# 03_DCDC_BOOST.net
KiCad netlist of a schematic drawn in Altium Designer
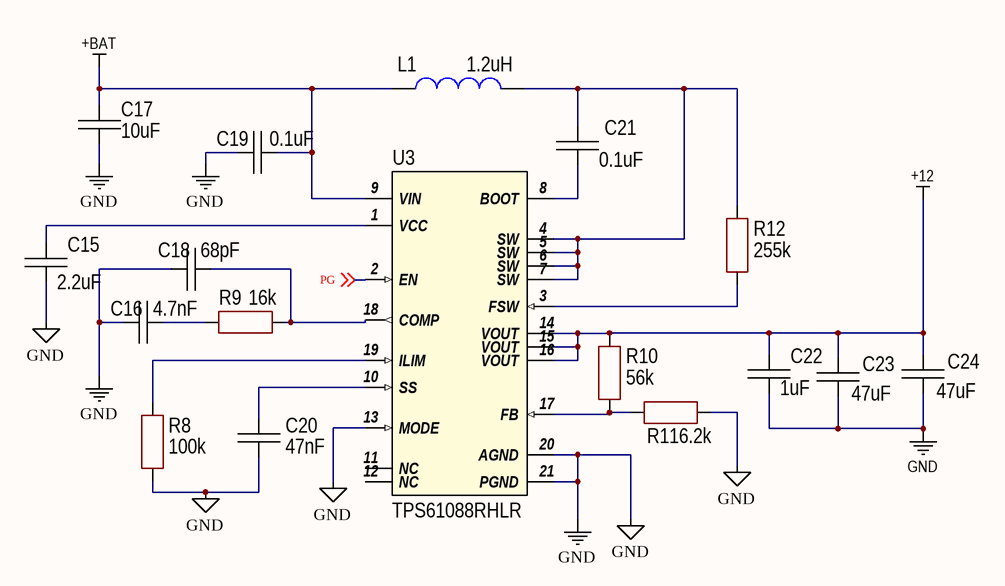
[diagram p0: 03_DCDC_BOOST.SchDoc]

(export (version "E")
  (design (tool "Eeschema 10.0.6"))
  (components
    (comp (ref "C15")
      (value "2.2uF")
      (footprint "CAP: 0805")
      (fields
        (field (name "MANUFACTURER") "Yageo")
        (field (name "PARTNUMBER") "CC0805KRX7R7BB104")
        (field (name "VALUEMANUFACTURERPARTNUMBER") "Ceramic capacitor, 2.2uF, X7R, ±10%, 16V, 0805, -55...+125°C")
      )
      (libsource (lib "capacitor") (part "Ceramic_0805"))
    )
    (comp (ref "C16")
      (value "4.7nF")
      (footprint "CAP: 0805")
      (fields
        (field (name "MANUFACTURER") "Yageo")
        (field (name "PARTNUMBER") "CC0805KRX7R7BB104")
        (field (name "VALUEMANUFACTURERPARTNUMBER") "Ceramic capacitor, 4.7nF, X7R, ±10%, 16V, 0805, -55...+125°C")
      )
      (libsource (lib "capacitor") (part "Ceramic_0805"))
    )
    (comp (ref "C17")
      (value "10uF")
      (footprint "CAP: 1206")
      (fields
        (field (name "MANUFACTURER") "Yageo")
        (field (name "PARTNUMBER") "CC1206KRX7R9BB104")
        (field (name "VALUEMANUFACTURERPARTNUMBER") "Ceramic capacitor, 10uF, X7R, ±10%, 50V, 1206, -55...+125°C")
      )
      (libsource (lib "capacitor") (part "Ceramic_1206"))
    )
    (comp (ref "C18")
      (value "68pF")
      (footprint "CAP: 0805")
      (fields
        (field (name "MANUFACTURER") "Yageo")
        (field (name "PARTNUMBER") "CC0805KRX7R7BB104")
        (field (name "VALUEMANUFACTURERPARTNUMBER") "Ceramic capacitor, 68pF, X7R, ±10%, 16V, 0805, -55...+125°C")
      )
      (libsource (lib "capacitor") (part "Ceramic_0805"))
    )
    (comp (ref "C19")
      (value "0.1uF")
      (footprint "CAP: 0603")
      (fields
        (field (name "MANUFACTURER") "Yageo")
        (field (name "PARTNUMBER") "CC0603KRX7R7BB104")
        (field (name "VALUEMANUFACTURERPARTNUMBER") "Ceramic capacitor, 0.1uF, X7R, ±10%, 16V, 0603, -55...+125°C")
      )
      (libsource (lib "capacitor") (part "Ceramic_0603"))
    )
    (comp (ref "C20")
      (value "47nF")
      (footprint "CAP: 0603")
      (fields
        (field (name "MANUFACTURER") "Yageo")
        (field (name "PARTNUMBER") "CC0603KRX7R7BB104")
        (field (name "VALUEMANUFACTURERPARTNUMBER") "Ceramic capacitor, 47nF, X7R, ±10%, 16V, 0603, -55...+125°C")
      )
      (libsource (lib "capacitor") (part "Ceramic_0603"))
    )
    (comp (ref "C21")
      (value "0.1uF")
      (footprint "CAP: 1210")
      (fields
        (field (name "MANUFACTURER") "Yageo")
        (field (name "PARTNUMBER") "CC1210KKX7R9BB104")
        (field (name "VALUEMANUFACTURERPARTNUMBER") "Ceramic capacitor, 0.1uF, X7R, ±10%, 50V, 1210, -55...+125°C")
      )
      (libsource (lib "capacitor") (part "Ceramic_1210"))
    )
    (comp (ref "C22")
      (value "1uF")
      (footprint "CAP: 0805")
      (fields
        (field (name "MANUFACTURER") "Yageo")
        (field (name "PARTNUMBER") "CC0805KRX7R7BB104")
        (field (name "VALUEMANUFACTURERPARTNUMBER") "Ceramic capacitor, 1uF, X7R, ±10%, 16V, 0805, -55...+125°C")
      )
      (libsource (lib "capacitor") (part "Ceramic_0805"))
    )
    (comp (ref "C23")
      (value "47uF")
      (footprint "CAP: 1206")
      (fields
        (field (name "MANUFACTURER") "Yageo")
        (field (name "PARTNUMBER") "CC1206KRX7R9BB104")
        (field (name "VALUEMANUFACTURERPARTNUMBER") "Ceramic capacitor, 47uF, X7R, ±10%, 50V, 1206, -55...+125°C")
      )
      (libsource (lib "capacitor") (part "Ceramic_1206"))
    )
    (comp (ref "C24")
      (value "47uF")
      (footprint "CAP: 1206")
      (fields
        (field (name "MANUFACTURER") "Yageo")
        (field (name "PARTNUMBER") "CC1206KRX7R9BB104")
        (field (name "VALUEMANUFACTURERPARTNUMBER") "Ceramic capacitor, 47uF, X7R, ±10%, 50V, 1206, -55...+125°C")
      )
      (libsource (lib "capacitor") (part "Ceramic_1206"))
    )
    (comp (ref "L1")
      (value "1.2uH")
      (footprint "IND: SRP1265A")
      (fields
        (field (name "MANUFACTURER") "Bourns")
        (field (name "PARTNUMBER") "SRP1265A-4R7M")
        (field (name "VALUEMANUFACTURERPARTNUMBER") "Fixed inductor, 1.2uH, ±20%, SRP1265A, 13.5A, -40...+150°C")
      )
      (libsource (lib "inductor") (part "Inductor_SRP1265A"))
    )
    (comp (ref "R8")
      (value "100k")
      (footprint "RES: 0603")
      (fields
        (field (name "MANUFACTURER") "Yageo")
        (field (name "PARTNUMBER") "RC0603JR-07100RL")
        (field (name "VALUEMANUFACTURERPARTNUMBER") "Resistor film, 100k, ±5%, 0603, 0.1W, -55...+125°C")
      )
      (libsource (lib "resistor") (part "Resistor_0603"))
    )
    (comp (ref "R9")
      (value "16k")
      (footprint "RES: 0603")
      (fields
        (field (name "MANUFACTURER") "Yageo")
        (field (name "PARTNUMBER") "RC0603JR-07100RL")
        (field (name "VALUEMANUFACTURERPARTNUMBER") "Resistor film, 16k, ±5%, 0603, 0.1W, -55...+125°C")
      )
      (libsource (lib "") (part "Resistor_0603_1"))
    )
    (comp (ref "R10")
      (value "56k")
      (footprint "RES: 0603")
      (fields
        (field (name "MANUFACTURER") "Yageo")
        (field (name "PARTNUMBER") "RC0603JR-07100RL")
        (field (name "VALUEMANUFACTURERPARTNUMBER") "Resistor film, 56k, ±5%, 0603, 0.1W, -55...+125°C")
      )
      (libsource (lib "resistor") (part "Resistor_0603"))
    )
    (comp (ref "R11")
      (value "6.2k")
      (footprint "RES: 0603")
      (fields
        (field (name "MANUFACTURER") "Yageo")
        (field (name "PARTNUMBER") "RC0603JR-07100RL")
        (field (name "VALUEMANUFACTURERPARTNUMBER") "Resistor film, 6.2k, ±5%, 0603, 0.1W, -55...+125°C")
      )
      (libsource (lib "") (part "Resistor_0603_1"))
    )
    (comp (ref "R12")
      (value "255k")
      (footprint "RES: 0603")
      (fields
        (field (name "MANUFACTURER") "Yageo")
        (field (name "PARTNUMBER") "RC0603JR-07100RL")
        (field (name "VALUEMANUFACTURERPARTNUMBER") "Resistor film, 255k, ±5%, 0603, 0.1W, -55...+125°C")
      )
      (libsource (lib "resistor") (part "Resistor_0603"))
    )
    (comp (ref "U3")
      (value "TPS61088RHLR")
      (footprint "RHL0020A")
      (description "10-A Fully-Integrated Synchronous Boost Converter 20-VQFN -40 to 125")
      (fields
        (field (name "ALTERNATE_PARTNUMBER") "TPS61088RHLT")
        (field (name "MANUFACTURER") "Texas Instruments")
        (field (name "COPYRIGHT") "Copyright (C) 2026 Ultra Librarian. All rights reserved.")
      )
      (libsource (lib "TPS61088RHLR") (part "TPS61088RHLR"))
    )
  )
  (nets
    (net (code "1") (name "+12") (class "Default")
      (node (ref "C22") (pin "2") (pinfunction "2_2") (pintype "passive"))
      (node (ref "C23") (pin "2") (pinfunction "2_2") (pintype "passive"))
      (node (ref "C24") (pin "2") (pinfunction "2_2") (pintype "passive"))
      (node (ref "R10") (pin "2") (pinfunction "2_2") (pintype "passive"))
      (node (ref "U3") (pin "14") (pinfunction "VOUT_14") (pintype "power_in"))
      (node (ref "U3") (pin "15") (pinfunction "VOUT_15") (pintype "power_in"))
      (node (ref "U3") (pin "16") (pinfunction "VOUT_16") (pintype "power_in"))
    )
    (net (code "2") (name "+BAT") (class "Default")
      (node (ref "C17") (pin "1") (pinfunction "1_1") (pintype "passive"))
      (node (ref "C19") (pin "1") (pinfunction "1_1") (pintype "passive"))
      (node (ref "L1") (pin "2") (pinfunction "2_2") (pintype "passive"))
      (node (ref "U3") (pin "9") (pinfunction "VIN_9") (pintype "power_in"))
    )
    (net (code "3") (name "GND") (class "Default")
      (node (ref "C15") (pin "1") (pinfunction "1_1") (pintype "passive"))
      (node (ref "C16") (pin "2") (pinfunction "2_2") (pintype "passive"))
      (node (ref "C17") (pin "2") (pinfunction "2_2") (pintype "passive"))
      (node (ref "C18") (pin "2") (pinfunction "2_2") (pintype "passive"))
      (node (ref "C19") (pin "2") (pinfunction "2_2") (pintype "passive"))
      (node (ref "C20") (pin "1") (pinfunction "1_1") (pintype "passive"))
      (node (ref "C22") (pin "1") (pinfunction "1_1") (pintype "passive"))
      (node (ref "C23") (pin "1") (pinfunction "1_1") (pintype "passive"))
      (node (ref "C24") (pin "1") (pinfunction "1_1") (pintype "passive"))
      (node (ref "R11") (pin "2") (pinfunction "2_2") (pintype "passive"))
      (node (ref "R8") (pin "1") (pinfunction "1_1") (pintype "passive"))
      (node (ref "U3") (pin "13") (pinfunction "MODE_13") (pintype "input"))
      (node (ref "U3") (pin "20") (pinfunction "AGND_20") (pintype "power_in"))
      (node (ref "U3") (pin "21") (pinfunction "PGND_21") (pintype "power_in"))
    )
    (net (code "4") (name "Net-(C16-Pad1)") (class "Default")
      (node (ref "C16") (pin "1") (pinfunction "1_1") (pintype "passive"))
      (node (ref "R9") (pin "1") (pinfunction "1_1") (pintype "passive"))
    )
    (net (code "5") (name "Net-(C21-Pad2)") (class "Default")
      (node (ref "C21") (pin "2") (pinfunction "2_2") (pintype "passive"))
      (node (ref "L1") (pin "1") (pinfunction "1_1") (pintype "passive"))
      (node (ref "R12") (pin "2") (pinfunction "2_2") (pintype "passive"))
      (node (ref "U3") (pin "4") (pinfunction "SW_4") (pintype "power_in"))
      (node (ref "U3") (pin "5") (pinfunction "SW_5") (pintype "power_in"))
      (node (ref "U3") (pin "6") (pinfunction "SW_6") (pintype "power_in"))
      (node (ref "U3") (pin "7") (pinfunction "SW_7") (pintype "power_in"))
    )
    (net (code "6") (name "Net-(U3-BOOT)") (class "Default")
      (node (ref "C21") (pin "1") (pinfunction "1_1") (pintype "passive"))
      (node (ref "U3") (pin "8") (pinfunction "BOOT_8") (pintype "power_in"))
    )
    (net (code "7") (name "Net-(U3-COMP)") (class "Default")
      (node (ref "C18") (pin "1") (pinfunction "1_1") (pintype "passive"))
      (node (ref "R9") (pin "2") (pinfunction "2_2") (pintype "passive"))
      (node (ref "U3") (pin "18") (pinfunction "COMP_18") (pintype "output"))
    )
    (net (code "8") (name "Net-(U3-FB)") (class "Default")
      (node (ref "R10") (pin "1") (pinfunction "1_1") (pintype "passive"))
      (node (ref "R11") (pin "1") (pinfunction "1_1") (pintype "passive"))
      (node (ref "U3") (pin "17") (pinfunction "FB_17") (pintype "input"))
    )
    (net (code "9") (name "Net-(U3-FSW)") (class "Default")
      (node (ref "R12") (pin "1") (pinfunction "1_1") (pintype "passive"))
      (node (ref "U3") (pin "3") (pinfunction "FSW_3") (pintype "input"))
    )
    (net (code "10") (name "Net-(U3-ILIM)") (class "Default")
      (node (ref "R8") (pin "2") (pinfunction "2_2") (pintype "passive"))
      (node (ref "U3") (pin "19") (pinfunction "ILIM_19") (pintype "input"))
    )
    (net (code "11") (name "Net-(U3-SS)") (class "Default")
      (node (ref "C20") (pin "2") (pinfunction "2_2") (pintype "passive"))
      (node (ref "U3") (pin "10") (pinfunction "SS_10") (pintype "input"))
    )
    (net (code "12") (name "Net-(U3-VCC)") (class "Default")
      (node (ref "C15") (pin "2") (pinfunction "2_2") (pintype "passive"))
      (node (ref "U3") (pin "1") (pinfunction "VCC_1") (pintype "power_in"))
    )
    (net (code "13") (name "PG") (class "Default")
      (node (ref "U3") (pin "2") (pinfunction "EN_2") (pintype "input"))
    )
    (net (code "14") (name "unconnected-(U3-NC-Pad11)") (class "Default")
      (node (ref "U3") (pin "11") (pinfunction "NC_11") (pintype "passive"))
    )
    (net (code "15") (name "unconnected-(U3-NC-Pad12)") (class "Default")
      (node (ref "U3") (pin "12") (pinfunction "NC_12") (pintype "passive"))
    )
  )
)
